# USBPWR_SWITCH_TPS2051.net
KiCad netlist of a schematic drawn in Altium Designer
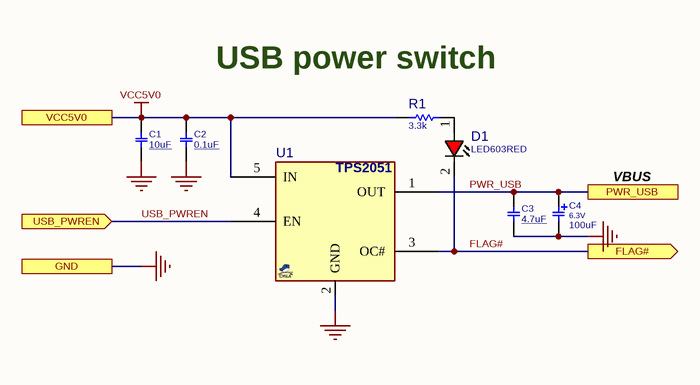
[diagram p0: USBPWR_SWITCH_TPS2051.SchDoc]

(export (version "E")
  (design (tool "Eeschema 10.0.6"))
  (components
    (comp (ref "C1")
      (value "10uF")
      (footprint "C0603")
      (description "C0402, MLCC, 10uF, 25V")
      (fields (field (name "MANF") "Murata"))
      (libsource (lib "mlcc_smd_passive") (part "CAP_SMD_MLCC"))
    )
    (comp (ref "C2")
      (value "0.1uF")
      (footprint "C0402")
      (description "C0402, MLCC, 100nF, 25V")
      (fields (field (name "MANF") "Murata"))
      (libsource (lib "mlcc_smd_passive") (part "CAP_SMD_MLCC"))
    )
    (comp (ref "C3")
      (value "4.7uF")
      (footprint "C0402")
      (description "C0402, MLCC, 4.7uF, 25V")
      (fields (field (name "MANF") "Murata"))
      (libsource (lib "mlcc_smd_passive") (part "CAP_SMD_MLCC"))
    )
    (comp (ref "C4")
      (value "100uF")
      (footprint "C_TN_3528")
      (description "CAP, SMD, TAN,")
      (fields (field (name "PARAM2") "6.3V"))
      (libsource (lib "passive_smd") (part "CAP_SMD_TAN_3528"))
    )
    (comp (ref "D1")
      (value "LED603RED")
      (footprint "LED0603RED")
      (description "LED, SMD, 0603, RED")
      (fields (field (name "MANF") "MANF") (field (name "MANF_P#") "MANF_PART#"))
      (libsource (lib "led(diode)") (part "LED_SMD_0603_RED"))
    )
    (comp (ref "R1")
      (value "3.3k")
      (footprint "R0402")
      (description "RESISTOR, SMD")
      (libsource (lib "res_smd_passive") (part "RES_SMD"))
    )
    (comp (ref "U1")
      (value "TPS2051")
      (footprint "SOT23_5")
      (description "LOAD SW,")
      (fields (field (name "MANF") "TI") (field (name "MANF_P#") "TPS2051BDBV"))
      (libsource (lib "power_load_switch") (part "TPS2051_SOT23"))
    )
  )
  (nets
    (net (code "1") (name "/FLAG#") (class "Default")
      (node (ref "D1") (pin "2") (pinfunction "CATHODE_2") (pintype "passive"))
      (node (ref "U1") (pin "3") (pinfunction "OC#_3") (pintype "passive"))
    )
    (net (code "2") (name "/PWR_USB") (class "Default")
      (node (ref "C3") (pin "2") (pinfunction "2_2") (pintype "passive"))
      (node (ref "C4") (pin "1") (pinfunction "1_1") (pintype "passive"))
      (node (ref "U1") (pin "1") (pinfunction "OUT_1") (pintype "passive"))
    )
    (net (code "3") (name "/USB_PWREN") (class "Default")
      (node (ref "U1") (pin "4") (pinfunction "EN_4") (pintype "passive"))
    )
    (net (code "4") (name "GND") (class "Default")
      (node (ref "C1") (pin "2") (pinfunction "2_2") (pintype "passive"))
      (node (ref "C2") (pin "2") (pinfunction "2_2") (pintype "passive"))
      (node (ref "C3") (pin "1") (pinfunction "1_1") (pintype "passive"))
      (node (ref "C4") (pin "2") (pinfunction "2_2") (pintype "passive"))
      (node (ref "U1") (pin "2") (pinfunction "GND_2") (pintype "power_in"))
    )
    (net (code "5") (name "Net-(D1-ANODE)") (class "Default")
      (node (ref "D1") (pin "1") (pinfunction "ANODE_1") (pintype "passive"))
      (node (ref "R1") (pin "2") (pinfunction "2_2") (pintype "passive"))
    )
    (net (code "6") (name "VCC5V0") (class "Default")
      (node (ref "C1") (pin "1") (pinfunction "1_1") (pintype "passive"))
      (node (ref "C2") (pin "1") (pinfunction "1_1") (pintype "passive"))
      (node (ref "R1") (pin "1") (pinfunction "1_1") (pintype "passive"))
      (node (ref "U1") (pin "5") (pinfunction "IN_5") (pintype "passive"))
    )
  )
)
